# AVRISP2TC.net
KiCad netlist of a schematic drawn in EAGLE
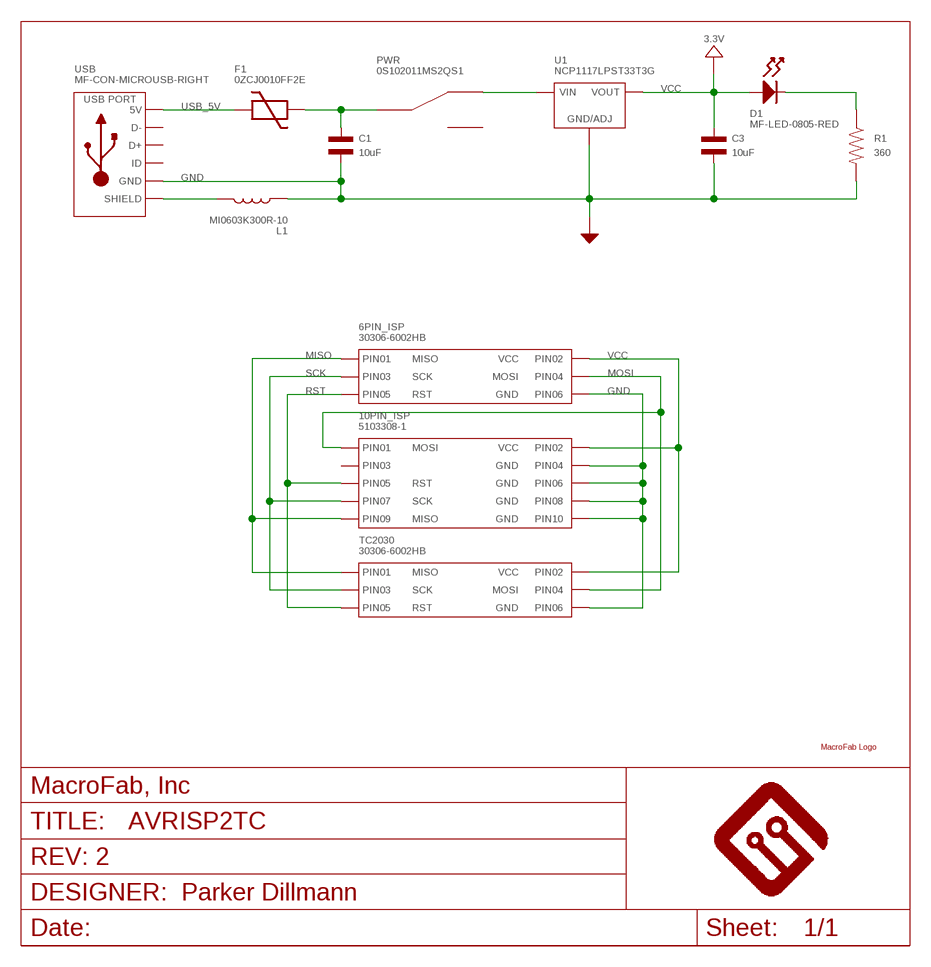
[diagram p0: schematic, sheet 1]

(export (version "E")
  (design (tool "Eeschema 10.0.6"))
  (components
    (comp (ref "6PIN_ISP")
      (value "30306-6002HB")
      (footprint "eagle-import:30306-6002HB")
      (fields
        (field (name "LABEL01") "MISO")
        (field (name "LABEL02") "VCC")
        (field (name "LABEL03") "SCK")
        (field (name "LABEL04") "MOSI")
        (field (name "LABEL05") "RST")
        (field (name "LABEL06") "GND")
      )
      (libsource (lib "eagle-import") (part "CON_02X03_30306-6002HB"))
    )
    (comp (ref "10PIN_ISP")
      (value "5103308-1")
      (footprint "eagle-import:5103308-1")
      (fields
        (field (name "LABEL01") "MOSI")
        (field (name "LABEL02") "VCC")
        (field (name "LABEL04") "GND")
        (field (name "LABEL05") "RST")
        (field (name "LABEL06") "GND")
        (field (name "LABEL07") "SCK")
        (field (name "LABEL08") "GND")
        (field (name "LABEL09") "MISO")
        (field (name "LABEL10") "GND")
      )
      (libsource (lib "eagle-import") (part "CON_02X05_5103308-1"))
    )
    (comp (ref "C1")
      (value "10uF")
      (footprint "eagle-import:C1206")
      (fields (field (name "MPN") "MF-CAP-1206-10uF"))
      (libsource (lib "eagle-import") (part "CAPACITOR_NP_1206"))
    )
    (comp (ref "C3")
      (value "10uF")
      (footprint "eagle-import:C1206")
      (fields (field (name "MPN") "MF-CAP-1206-10uF"))
      (libsource (lib "eagle-import") (part "CAPACITOR_NP_1206"))
    )
    (comp (ref "D1")
      (value "MF-LED-0805-RED")
      (footprint "eagle-import:LED0805")
      (fields (field (name "HOUSEPART") "YES"))
      (libsource (lib "eagle-import") (part "LED_SINGLE-0805-RED"))
    )
    (comp (ref "F1")
      (value "0ZCJ0010FF2E")
      (footprint "eagle-import:1206")
      (libsource (lib "eagle-import") (part "PTC_FUSE_1206"))
    )
    (comp (ref "FRAME1")
      (value "MF_FRAMEDEFAULT")
      (footprint "eagle-import:MF_FRAME_DEFAULT")
      (fields
        (field (name "HOUSEPART") "0")
        (field (name "DNAME") "Parker Dillmann")
        (field (name "REVNUM") "REV: 2")
      )
      (libsource (lib "eagle-import") (part "MF_FRAMEDEFAULT"))
    )
    (comp (ref "L1")
      (value "MI0603K300R-10")
      (footprint "eagle-import:L0603")
      (fields (field (name "MPN") "MI0603K300R-10"))
      (libsource (lib "eagle-import") (part "INDUCTOR_0603"))
    )
    (comp (ref "PWR")
      (value "0S102011MS2QS1")
      (footprint "eagle-import:0S102011MS2QS1")
      (libsource (lib "eagle-import") (part "SPDT_0S102011MS2QS1"))
    )
    (comp (ref "R1")
      (value "360")
      (footprint "eagle-import:R0805")
      (fields (field (name "MPN") "MF-RES-0805-360"))
      (libsource (lib "eagle-import") (part "RESISTOR_0805"))
    )
    (comp (ref "TC2030")
      (value "30306-6002HB")
      (footprint "eagle-import:30306-6002HB")
      (fields
        (field (name "LABEL01") "MISO")
        (field (name "LABEL02") "VCC")
        (field (name "LABEL03") "SCK")
        (field (name "LABEL04") "MOSI")
        (field (name "LABEL05") "RST")
        (field (name "LABEL06") "GND")
      )
      (libsource (lib "eagle-import") (part "CON_02X03_30306-6002HB"))
    )
    (comp (ref "U$3")
      (value "MF_LOGOLOGO_MEDIUM")
      (footprint "eagle-import:MF_LOGO_MEDIUM")
      (libsource (lib "eagle-import") (part "MF_LOGOLOGO_MEDIUM"))
    )
    (comp (ref "U1")
      (value "NCP1117LPST33T3G")
      (footprint "eagle-import:SOT-223-3")
      (fields (field (name "HOUSEPART") "NO"))
      (libsource (lib "eagle-import") (part "NCP1117LPST33T3G"))
    )
    (comp (ref "USB")
      (value "MF-CON-MICROUSB-RIGHT")
      (footprint "eagle-import:MICROUSB-RIGHT")
      (fields (field (name "HOUSEPART") "YES"))
      (libsource (lib "eagle-import") (part "USB_MICRO_RIGHT"))
    )
  )
  (nets
    (net (code "1") (name "/MISO") (class "Default")
      (node (ref "10PIN_ISP") (pin "9") (pinfunction "PIN9_9") (pintype "bidirectional"))
      (node (ref "6PIN_ISP") (pin "1") (pinfunction "PIN1_1") (pintype "bidirectional"))
      (node (ref "TC2030") (pin "1") (pinfunction "PIN1_1") (pintype "bidirectional"))
    )
    (net (code "2") (name "/MOSI") (class "Default")
      (node (ref "10PIN_ISP") (pin "1") (pinfunction "PIN1_1") (pintype "bidirectional"))
      (node (ref "6PIN_ISP") (pin "4") (pinfunction "PIN4_4") (pintype "bidirectional"))
      (node (ref "TC2030") (pin "4") (pinfunction "PIN4_4") (pintype "bidirectional"))
    )
    (net (code "3") (name "/RST") (class "Default")
      (node (ref "10PIN_ISP") (pin "5") (pinfunction "PIN5_5") (pintype "bidirectional"))
      (node (ref "6PIN_ISP") (pin "5") (pinfunction "PIN5_5") (pintype "bidirectional"))
      (node (ref "TC2030") (pin "5") (pinfunction "PIN5_5") (pintype "bidirectional"))
    )
    (net (code "4") (name "/SCK") (class "Default")
      (node (ref "10PIN_ISP") (pin "7") (pinfunction "PIN7_7") (pintype "bidirectional"))
      (node (ref "6PIN_ISP") (pin "3") (pinfunction "PIN3_3") (pintype "bidirectional"))
      (node (ref "TC2030") (pin "3") (pinfunction "PIN3_3") (pintype "bidirectional"))
    )
    (net (code "5") (name "/USB_5V") (class "Default")
      (node (ref "F1") (pin "1") (pinfunction "P$1_1") (pintype "bidirectional"))
      (node (ref "USB") (pin "1") (pinfunction "5V_1") (pintype "power_in"))
    )
    (net (code "6") (name "3.3V") (class "Default")
      (node (ref "10PIN_ISP") (pin "2") (pinfunction "PIN2_2") (pintype "bidirectional"))
      (node (ref "6PIN_ISP") (pin "2") (pinfunction "PIN2_2") (pintype "bidirectional"))
      (node (ref "C3") (pin "P$1") (pinfunction "P$1_P$1") (pintype "passive"))
      (node (ref "D1") (pin "ANODE") (pinfunction "ANODE_ANODE") (pintype "power_in"))
      (node (ref "TC2030") (pin "2") (pinfunction "PIN2_2") (pintype "bidirectional"))
      (node (ref "U1") (pin "P$1") (pinfunction "VOUT_P$1") (pintype "bidirectional"))
      (node (ref "U1") (pin "P$3") (pinfunction "VOUT_P$3") (pintype "bidirectional"))
    )
    (net (code "7") (name "GND_RAIL") (class "Default")
      (node (ref "10PIN_ISP") (pin "10") (pinfunction "PIN10_10") (pintype "bidirectional"))
      (node (ref "10PIN_ISP") (pin "4") (pinfunction "PIN4_4") (pintype "bidirectional"))
      (node (ref "10PIN_ISP") (pin "6") (pinfunction "PIN6_6") (pintype "bidirectional"))
      (node (ref "10PIN_ISP") (pin "8") (pinfunction "PIN8_8") (pintype "bidirectional"))
      (node (ref "6PIN_ISP") (pin "6") (pinfunction "PIN6_6") (pintype "bidirectional"))
      (node (ref "C1") (pin "P$2") (pinfunction "P$2_P$2") (pintype "passive"))
      (node (ref "C3") (pin "P$2") (pinfunction "P$2_P$2") (pintype "passive"))
      (node (ref "L1") (pin "P$1") (pinfunction "P$1_P$1") (pintype "passive"))
      (node (ref "R1") (pin "P$2") (pinfunction "P$2_P$2") (pintype "passive"))
      (node (ref "TC2030") (pin "6") (pinfunction "PIN6_6") (pintype "bidirectional"))
      (node (ref "U1") (pin "P$2") (pinfunction "GND/ADJ_P$2") (pintype "bidirectional"))
      (node (ref "USB") (pin "5") (pinfunction "GND_5") (pintype "power_in"))
    )
    (net (code "8") (name "Net-(D1-PadCATHODE)") (class "Default")
      (node (ref "D1") (pin "CATHODE") (pinfunction "CATHODE_CATHODE") (pintype "power_in"))
      (node (ref "R1") (pin "P$1") (pinfunction "P$1_P$1") (pintype "passive"))
    )
    (net (code "9") (name "Net-(F1-P$2)") (class "Default")
      (node (ref "C1") (pin "P$1") (pinfunction "P$1_P$1") (pintype "passive"))
      (node (ref "F1") (pin "2") (pinfunction "P$2_2") (pintype "bidirectional"))
      (node (ref "PWR") (pin "2") (pinfunction "C_2") (pintype "bidirectional"))
    )
    (net (code "10") (name "Net-(L1-PadP$2)") (class "Default")
      (node (ref "L1") (pin "P$2") (pinfunction "P$2_P$2") (pintype "passive"))
      (node (ref "USB") (pin "S1") (pinfunction "SLD_S1") (pintype "power_in"))
      (node (ref "USB") (pin "S2") (pinfunction "SLD_S2") (pintype "power_in"))
      (node (ref "USB") (pin "S3") (pinfunction "SLD_S3") (pintype "power_in"))
      (node (ref "USB") (pin "S4") (pinfunction "SLD_S4") (pintype "power_in"))
      (node (ref "USB") (pin "S5") (pinfunction "SLD_S5") (pintype "power_in"))
      (node (ref "USB") (pin "S6") (pinfunction "SLD_S6") (pintype "power_in"))
    )
    (net (code "11") (name "Net-(U1-VIN)") (class "Default")
      (node (ref "PWR") (pin "1") (pinfunction "1_1") (pintype "bidirectional"))
      (node (ref "U1") (pin "P$4") (pinfunction "VIN_P$4") (pintype "bidirectional"))
    )
    (net (code "12") (name "unconnected-(10PIN_ISP-PIN3-Pad3)") (class "Default")
      (node (ref "10PIN_ISP") (pin "3") (pinfunction "PIN3_3") (pintype "bidirectional"))
    )
    (net (code "13") (name "unconnected-(PWR-2-Pad3)") (class "Default")
      (node (ref "PWR") (pin "3") (pinfunction "2_3") (pintype "bidirectional"))
    )
    (net (code "14") (name "unconnected-(USB-D+-Pad3)") (class "Default")
      (node (ref "USB") (pin "3") (pinfunction "D+_3") (pintype "bidirectional"))
    )
    (net (code "15") (name "unconnected-(USB-D--Pad2)") (class "Default")
      (node (ref "USB") (pin "2") (pinfunction "D-_2") (pintype "bidirectional"))
    )
    (net (code "16") (name "unconnected-(USB-ID-Pad4)") (class "Default")
      (node (ref "USB") (pin "4") (pinfunction "ID_4") (pintype "bidirectional"))
    )
  )
)
